# 4_39.net
KiCad netlist of a schematic drawn in EasyEDA
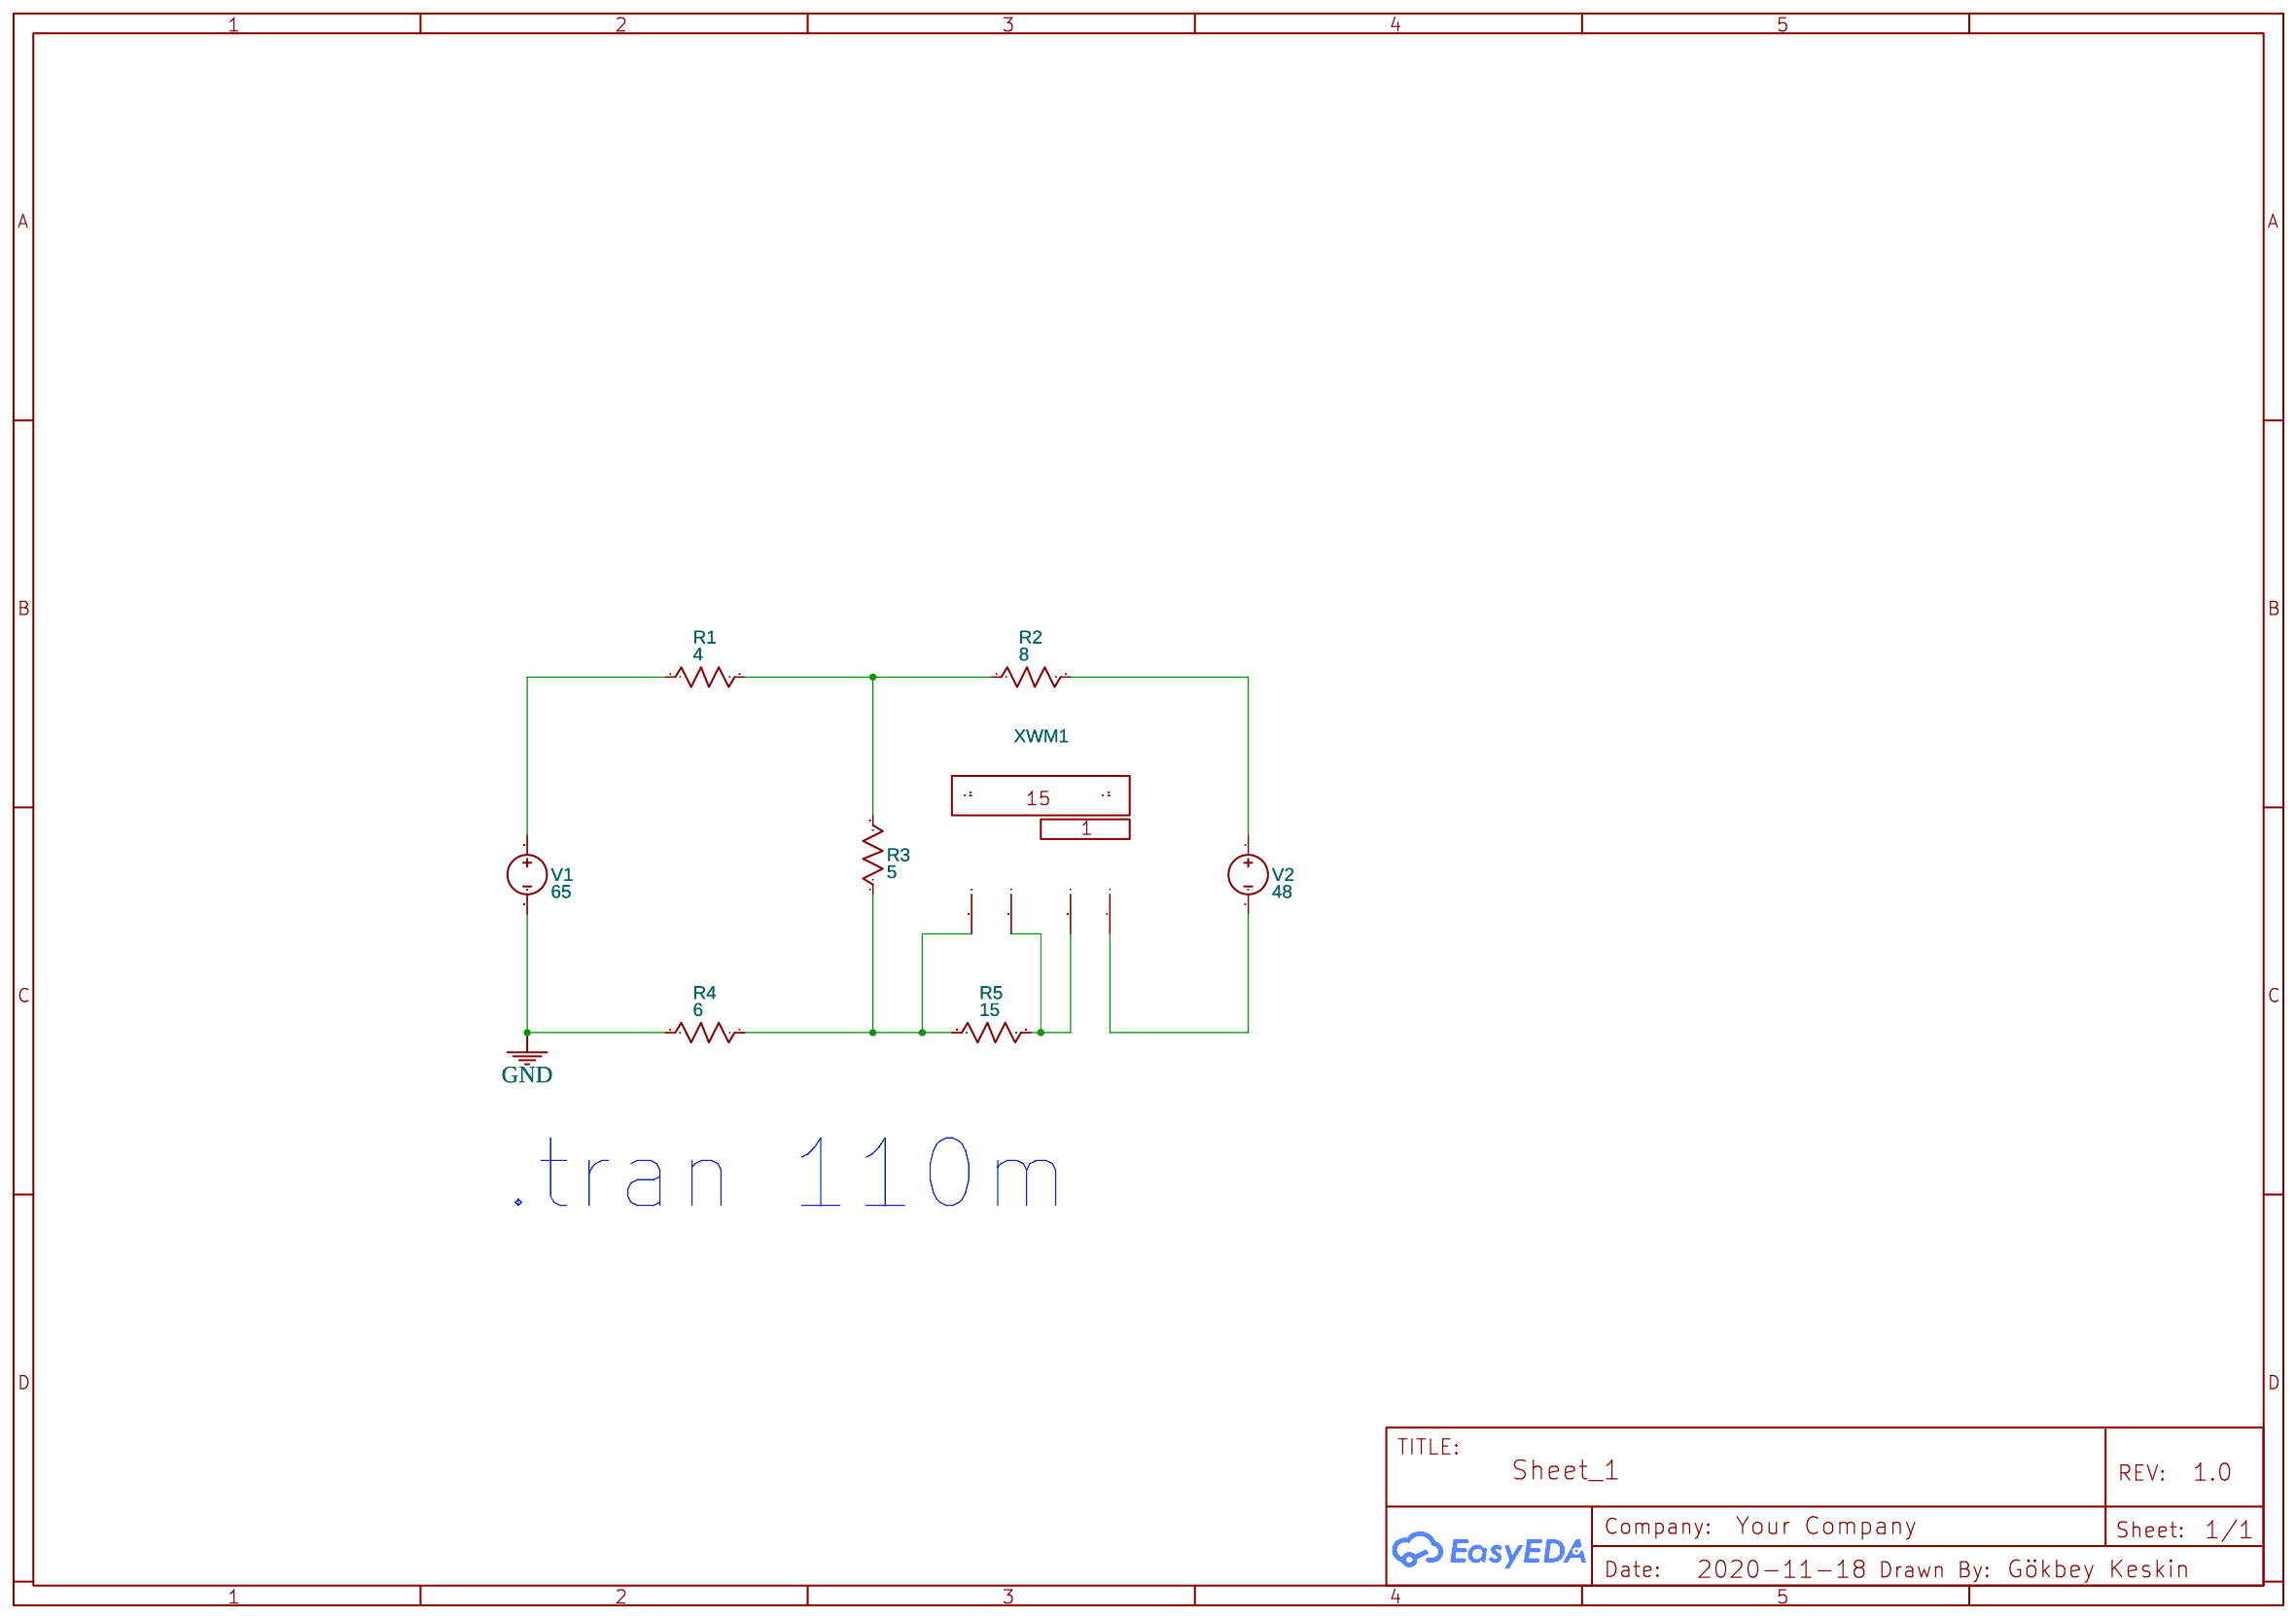
[diagram p0: schematic sheet]

(export (version "E")
  (design (tool "Eeschema 10.0.6"))
  (components
    (comp (ref "R1") (value "4") (libsource (lib "") (part "Resistor_US_1")))
    (comp (ref "R2") (value "8") (libsource (lib "") (part "Resistor_US_1")))
    (comp (ref "R3") (value "5") (libsource (lib "") (part "Resistor_US_2")))
    (comp (ref "R4") (value "6") (libsource (lib "") (part "Resistor_US")))
    (comp (ref "R5") (value "15") (libsource (lib "") (part "Resistor_US")))
    (comp (ref "V1") (value "65") (libsource (lib "") (part "VDC")))
    (comp (ref "V2") (value "48") (libsource (lib "") (part "VDC")))
    (comp (ref "XWM1") (value "Wattmeter") (libsource (lib "") (part "WATTMETER")))
  )
  (nets
    (net (code "1") (name "GND") (class "Default")
      (node (ref "R4") (pin "2") (pinfunction "2_2") (pintype "unspecified"))
      (node (ref "V1") (pin "2") (pinfunction "2_2") (pintype "unspecified"))
    )
    (net (code "2") (name "Net-(R1-Pad1)") (class "Default")
      (node (ref "R1") (pin "1") (pinfunction "1_1") (pintype "unspecified"))
      (node (ref "V1") (pin "1") (pinfunction "1_1") (pintype "unspecified"))
    )
    (net (code "3") (name "Net-(R1-Pad2)") (class "Default")
      (node (ref "R1") (pin "2") (pinfunction "2_2") (pintype "unspecified"))
      (node (ref "R2") (pin "1") (pinfunction "1_1") (pintype "unspecified"))
      (node (ref "R3") (pin "2") (pinfunction "2_2") (pintype "unspecified"))
    )
    (net (code "4") (name "Net-(R2-Pad2)") (class "Default")
      (node (ref "R2") (pin "2") (pinfunction "2_2") (pintype "unspecified"))
      (node (ref "V2") (pin "1") (pinfunction "1_1") (pintype "unspecified"))
    )
    (net (code "5") (name "Net-(XWM1-I+)") (class "Default")
      (node (ref "R5") (pin "1") (pinfunction "1_1") (pintype "unspecified"))
      (node (ref "XWM1") (pin "2") (pinfunction "V-_2") (pintype "unspecified"))
      (node (ref "XWM1") (pin "3") (pinfunction "I+_3") (pintype "unspecified"))
    )
    (net (code "6") (name "Net-(XWM1-I-)") (class "Default")
      (node (ref "V2") (pin "2") (pinfunction "2_2") (pintype "unspecified"))
      (node (ref "XWM1") (pin "4") (pinfunction "I-_4") (pintype "unspecified"))
    )
    (net (code "7") (name "Net-(XWM1-V+)") (class "Default")
      (node (ref "R3") (pin "1") (pinfunction "1_1") (pintype "unspecified"))
      (node (ref "R4") (pin "1") (pinfunction "1_1") (pintype "unspecified"))
      (node (ref "R5") (pin "2") (pinfunction "2_2") (pintype "unspecified"))
      (node (ref "XWM1") (pin "1") (pinfunction "V+_1") (pintype "unspecified"))
    )
    (net (code "8") (name "unconnected-(XWM1-PadP)") (class "Default")
      (node (ref "XWM1") (pin "P") (pinfunction "P_P") (pintype "unspecified"))
    )
    (net (code "9") (name "unconnected-(XWM1-PadPF)") (class "Default")
      (node (ref "XWM1") (pin "PF") (pinfunction "PF_PF") (pintype "unspecified"))
    )
  )
)
